# RGBchipLED_dip-borad.net
KiCad netlist of a schematic drawn in EAGLE
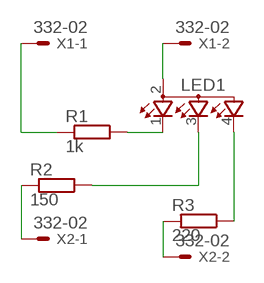
[diagram p0: schematic, sheet 1]

(export (version "E")
  (design (tool "Eeschema 10.0.6"))
  (components
    (comp (ref "LED1")
      (value "TOPLED-3")
      (footprint "eagle-import:P-LCC-4-3")
      (libsource (lib "eagle-import") (part "TOPLED-3"))
    )
    (comp (ref "R1")
      (value "1k")
      (footprint "eagle-import:SMK")
      (libsource (lib "eagle-import") (part "SMK"))
    )
    (comp (ref "R2")
      (value "150")
      (footprint "eagle-import:SMK")
      (libsource (lib "eagle-import") (part "SMK"))
    )
    (comp (ref "R3")
      (value "220")
      (footprint "eagle-import:SMK")
      (libsource (lib "eagle-import") (part "SMK"))
    )
    (comp (ref "X1")
      (value "332-02")
      (footprint "eagle-import:332-02")
      (libsource (lib "eagle-import") (part "332-02"))
    )
    (comp (ref "X2")
      (value "332-02")
      (footprint "eagle-import:332-02")
      (libsource (lib "eagle-import") (part "332-02"))
    )
  )
  (nets
    (net (code "1") (name "Net-(LED1-A2)") (class "Default")
      (node (ref "LED1") (pin "2") (pinfunction "A2_2") (pintype "passive"))
      (node (ref "X1") (pin "2") (pinfunction "S_2") (pintype "passive"))
    )
    (net (code "2") (name "Net-(LED1-CBLUE)") (class "Default")
      (node (ref "LED1") (pin "3") (pinfunction "CBLUE_3") (pintype "passive"))
      (node (ref "R2") (pin "1") (pinfunction "1_1") (pintype "passive"))
    )
    (net (code "3") (name "Net-(LED1-CGREEN)") (class "Default")
      (node (ref "LED1") (pin "4") (pinfunction "CGREEN_4") (pintype "passive"))
      (node (ref "R3") (pin "1") (pinfunction "1_1") (pintype "passive"))
    )
    (net (code "4") (name "Net-(LED1-CRED)") (class "Default")
      (node (ref "LED1") (pin "1") (pinfunction "CRED_1") (pintype "passive"))
      (node (ref "R1") (pin "1") (pinfunction "1_1") (pintype "passive"))
    )
    (net (code "5") (name "Net-(X1A-S)") (class "Default")
      (node (ref "R1") (pin "2") (pinfunction "2_2") (pintype "passive"))
      (node (ref "X1") (pin "1") (pinfunction "S_1") (pintype "passive"))
    )
    (net (code "6") (name "Net-(X2A-S)") (class "Default")
      (node (ref "R2") (pin "2") (pinfunction "2_2") (pintype "passive"))
      (node (ref "X2") (pin "1") (pinfunction "S_1") (pintype "passive"))
    )
    (net (code "7") (name "Net-(X2B-S)") (class "Default")
      (node (ref "R3") (pin "2") (pinfunction "2_2") (pintype "passive"))
      (node (ref "X2") (pin "2") (pinfunction "S_2") (pintype "passive"))
    )
  )
)
